# ft232.net
KiCad netlist of a schematic drawn in Altium Designer
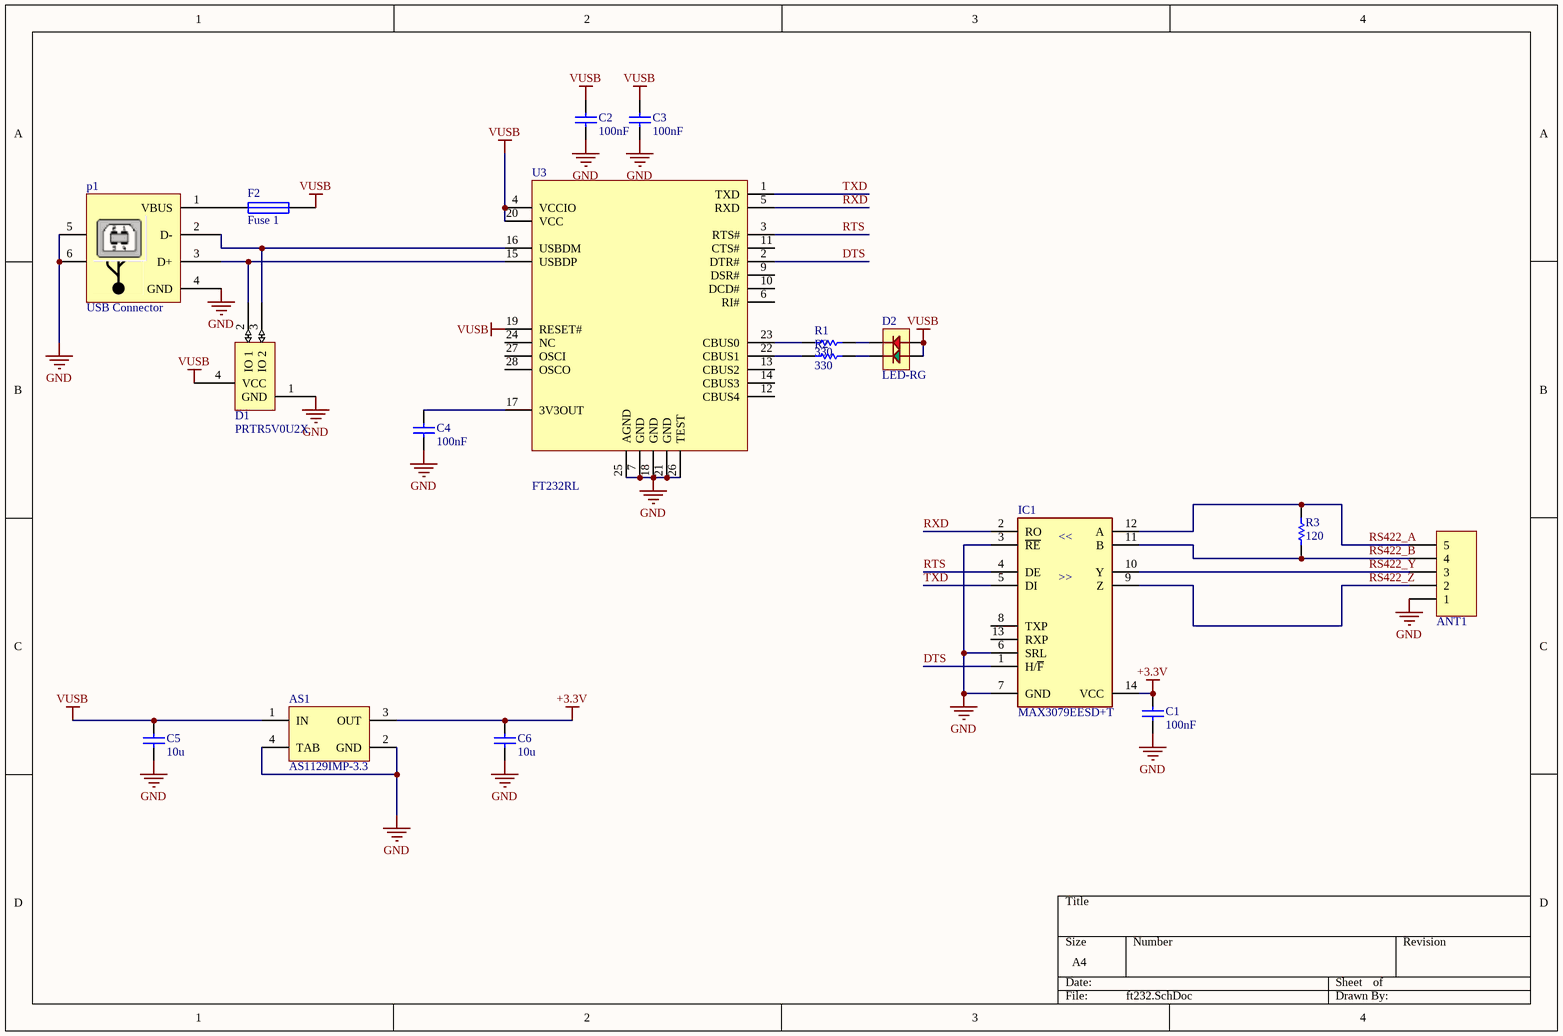
[diagram p0: ft232.SchDoc]

(export (version "E")
  (design (tool "Eeschema 10.0.6"))
  (components
    (comp (ref "ANT1") (value "CONN-5") (footprint "PH-5") (libsource (lib "ParsaLibrary") (part "CONN-5")))
    (comp (ref "AS1")
      (value "AS1129IMP-3.3")
      (footprint "SOT-223")
      (description "x.x Volt, 800mA Low-Dropout Linear Regulator, 4-pin SOT-223")
      (fields
        (field (name "PARTNUMBER") "LM1117IMP-3.3")
        (field (name "MANUFACTURER") "National Semiconductor")
        (field (name "PUBLISHER") "Altium Limited")
      )
      (libsource (lib "ParsaLibrary") (part "AS1129IMP-x.x"))
    )
    (comp (ref "C1")
      (value "100nF")
      (footprint "C603")
      (description "Capacitor")
      (fields (field (name "DESIGNER") "Parsa Malekpour"))
      (libsource (lib "ParsaLibrary") (part "Cap"))
    )
    (comp (ref "C2")
      (value "100nF")
      (footprint "c603")
      (description "Capacitor")
      (fields (field (name "DESIGNER") "Parsa Malekpour"))
      (libsource (lib "ParsaLibrary") (part "Cap"))
    )
    (comp (ref "C3")
      (value "100nF")
      (footprint "c603")
      (description "Capacitor")
      (fields (field (name "DESIGNER") "Parsa Malekpour"))
      (libsource (lib "ParsaLibrary") (part "Cap"))
    )
    (comp (ref "C4")
      (value "100nF")
      (footprint "c603")
      (description "Capacitor")
      (fields (field (name "DESIGNER") "Parsa Malekpour"))
      (libsource (lib "ParsaLibrary") (part "Cap"))
    )
    (comp (ref "C5")
      (value "10u")
      (footprint "C603")
      (description "Capacitor")
      (fields (field (name "DESIGNER") "Parsa Malekpour"))
      (libsource (lib "ParsaLibrary") (part "Cap"))
    )
    (comp (ref "C6")
      (value "10u")
      (footprint "C603")
      (description "Capacitor")
      (fields (field (name "DESIGNER") "Parsa Malekpour"))
      (libsource (lib "ParsaLibrary") (part "Cap"))
    )
    (comp (ref "D1")
      (value "PRTR5V0U2X")
      (footprint "SOT-143B")
      (description "Ultra low capacitance double rail-to-rail ESD protection diode")
      (libsource (lib "ParsaLibrary") (part "PRTR5V0U2X"))
    )
    (comp (ref "D2")
      (value "LED-RG")
      (footprint "LED-1210")
      (libsource (lib "ParsaLibrary") (part "LED-RG-4"))
    )
    (comp (ref "F2")
      (value "Fuse 1")
      (footprint "PTC-0805")
      (description "Fuse")
      (fields (field (name "PUBLISHER") "Altium Limited"))
      (libsource (lib "Miscellaneous Devices") (part "Fuse 1"))
    )
    (comp (ref "IC1")
      (value "MAX3079EESD+T")
      (footprint "SamacSys:SOIC127P600X175-14N")
      (description "Integrated Circuit")
      (fields (field (name "MOUSER PART NUMBER") "700-MAX3079EESDT"))
      (libsource (lib "SamacSys") (part "MAX3079EESD+T"))
    )
    (comp (ref "p1")
      (value "USB Connector")
      (footprint "USB2-B-R")
      (description "USB Connector-B Type")
      (fields (field (name "DESIGNER") "Eng. Saeid Jorablo"))
      (libsource (lib "ParsaLibrary") (part "USB2-B"))
    )
    (comp (ref "R1")
      (value "330")
      (footprint "R0603")
      (description "Resistor")
      (fields (field (name "DESIGNER") "Parsa Malekpour"))
      (libsource (lib "ParsaLibrary") (part "Resistor"))
    )
    (comp (ref "R2")
      (value "330")
      (footprint "R0603")
      (description "Resistor")
      (fields (field (name "DESIGNER") "Parsa Malekpour"))
      (libsource (lib "ParsaLibrary") (part "Resistor"))
    )
    (comp (ref "R3")
      (value "120")
      (footprint "R0603")
      (description "Resistor")
      (fields (field (name "DESIGNER") "Parsa Malekpour"))
      (libsource (lib "ParsaLibrary") (part "Resistor"))
    )
    (comp (ref "U3")
      (value "FT232RL")
      (footprint "SSOP-28N")
      (libsource (lib "ParsaLibrary") (part "FT232RL"))
    )
  )
  (nets
    (net (code "1") (name "+3.3V") (class "Default")
      (node (ref "AS1") (pin "3") (pinfunction "OUT_3") (pintype "power_in"))
      (node (ref "C1") (pin "2") (pinfunction "2_2") (pintype "passive"))
      (node (ref "C6") (pin "2") (pinfunction "2_2") (pintype "passive"))
      (node (ref "IC1") (pin "14") (pinfunction "VCC_14") (pintype "passive"))
    )
    (net (code "2") (name "/DTS") (class "Default")
      (node (ref "IC1") (pin "1") (pinfunction "H/~{F}_1") (pintype "passive"))
      (node (ref "U3") (pin "2") (pinfunction "DTR#_2") (pintype "passive"))
    )
    (net (code "3") (name "/RS422_A") (class "Default")
      (node (ref "ANT1") (pin "5") (pinfunction "5_5") (pintype "passive"))
      (node (ref "IC1") (pin "12") (pinfunction "A_12") (pintype "passive"))
      (node (ref "R3") (pin "2") (pinfunction "2_2") (pintype "passive"))
    )
    (net (code "4") (name "/RS422_B") (class "Default")
      (node (ref "ANT1") (pin "4") (pinfunction "4_4") (pintype "passive"))
      (node (ref "IC1") (pin "11") (pinfunction "B_11") (pintype "passive"))
      (node (ref "R3") (pin "1") (pinfunction "1_1") (pintype "passive"))
    )
    (net (code "5") (name "/RS422_Y") (class "Default")
      (node (ref "ANT1") (pin "3") (pinfunction "3_3") (pintype "passive"))
      (node (ref "IC1") (pin "10") (pinfunction "Y_10") (pintype "passive"))
    )
    (net (code "6") (name "/RS422_Z") (class "Default")
      (node (ref "ANT1") (pin "2") (pinfunction "2_2") (pintype "passive"))
      (node (ref "IC1") (pin "9") (pinfunction "Z_9") (pintype "passive"))
    )
    (net (code "7") (name "/RTS") (class "Default")
      (node (ref "IC1") (pin "4") (pinfunction "DE_4") (pintype "passive"))
      (node (ref "U3") (pin "3") (pinfunction "RTS#_3") (pintype "passive"))
    )
    (net (code "8") (name "/RXD") (class "Default")
      (node (ref "IC1") (pin "2") (pinfunction "RO_2") (pintype "passive"))
      (node (ref "U3") (pin "5") (pinfunction "RXD_5") (pintype "passive"))
    )
    (net (code "9") (name "/TXD") (class "Default")
      (node (ref "IC1") (pin "5") (pinfunction "DI_5") (pintype "passive"))
      (node (ref "U3") (pin "1") (pinfunction "TXD_1") (pintype "passive"))
    )
    (net (code "10") (name "GND") (class "Default")
      (node (ref "ANT1") (pin "1") (pinfunction "1_1") (pintype "passive"))
      (node (ref "AS1") (pin "2") (pinfunction "GND_2") (pintype "power_in"))
      (node (ref "AS1") (pin "4") (pinfunction "TAB_4") (pintype "power_in"))
      (node (ref "C1") (pin "1") (pinfunction "1_1") (pintype "passive"))
      (node (ref "C2") (pin "1") (pinfunction "1_1") (pintype "passive"))
      (node (ref "C3") (pin "1") (pinfunction "1_1") (pintype "passive"))
      (node (ref "C4") (pin "1") (pinfunction "1_1") (pintype "passive"))
      (node (ref "C5") (pin "1") (pinfunction "1_1") (pintype "passive"))
      (node (ref "C6") (pin "1") (pinfunction "1_1") (pintype "passive"))
      (node (ref "D1") (pin "1") (pinfunction "GND_1") (pintype "power_in"))
      (node (ref "IC1") (pin "3") (pinfunction "~{RE}_3") (pintype "passive"))
      (node (ref "IC1") (pin "6") (pinfunction "SRL_6") (pintype "passive"))
      (node (ref "IC1") (pin "7") (pinfunction "GND_7") (pintype "passive"))
      (node (ref "U3") (pin "18") (pinfunction "GND_18") (pintype "passive"))
      (node (ref "U3") (pin "21") (pinfunction "GND_21") (pintype "passive"))
      (node (ref "U3") (pin "25") (pinfunction "AGND_25") (pintype "passive"))
      (node (ref "U3") (pin "26") (pinfunction "TEST_26") (pintype "passive"))
      (node (ref "U3") (pin "7") (pinfunction "GND_7") (pintype "passive"))
      (node (ref "p1") (pin "4") (pinfunction "GND_4") (pintype "power_in"))
      (node (ref "p1") (pin "5") (pinfunction "5_5") (pintype "passive"))
      (node (ref "p1") (pin "6") (pinfunction "6_6") (pintype "passive"))
    )
    (net (code "11") (name "Net-(D1-IO_1)") (class "Default")
      (node (ref "D1") (pin "2") (pinfunction "IO_1_2") (pintype "bidirectional"))
      (node (ref "U3") (pin "15") (pinfunction "USBDP_15") (pintype "passive"))
      (node (ref "p1") (pin "3") (pinfunction "D+_3") (pintype "passive"))
    )
    (net (code "12") (name "Net-(D1-IO_2)") (class "Default")
      (node (ref "D1") (pin "3") (pinfunction "IO_2_3") (pintype "bidirectional"))
      (node (ref "U3") (pin "16") (pinfunction "USBDM_16") (pintype "passive"))
      (node (ref "p1") (pin "2") (pinfunction "D-_2") (pintype "passive"))
    )
    (net (code "13") (name "Net-(D2-GRN-C)") (class "Default")
      (node (ref "D2") (pin "4") (pinfunction "GRN-C_4") (pintype "passive"))
      (node (ref "R2") (pin "2") (pinfunction "2_2") (pintype "passive"))
    )
    (net (code "14") (name "Net-(D2-RED-C)") (class "Default")
      (node (ref "D2") (pin "3") (pinfunction "RED-C_3") (pintype "passive"))
      (node (ref "R1") (pin "2") (pinfunction "2_2") (pintype "passive"))
    )
    (net (code "15") (name "Net-(U3-3V3OUT)") (class "Default")
      (node (ref "C4") (pin "2") (pinfunction "2_2") (pintype "passive"))
      (node (ref "U3") (pin "17") (pinfunction "3V3OUT_17") (pintype "passive"))
    )
    (net (code "16") (name "Net-(U3-CBUS0)") (class "Default")
      (node (ref "R1") (pin "1") (pinfunction "1_1") (pintype "passive"))
      (node (ref "U3") (pin "23") (pinfunction "CBUS0_23") (pintype "passive"))
    )
    (net (code "17") (name "Net-(U3-CBUS1)") (class "Default")
      (node (ref "R2") (pin "1") (pinfunction "1_1") (pintype "passive"))
      (node (ref "U3") (pin "22") (pinfunction "CBUS1_22") (pintype "passive"))
    )
    (net (code "18") (name "Net-(p1-VBUS)") (class "Default")
      (node (ref "F2") (pin "1") (pinfunction "1_1") (pintype "passive"))
      (node (ref "p1") (pin "1") (pinfunction "VBUS_1") (pintype "power_in"))
    )
    (net (code "19") (name "VUSB") (class "Default")
      (node (ref "AS1") (pin "1") (pinfunction "IN_1") (pintype "power_in"))
      (node (ref "C2") (pin "2") (pinfunction "2_2") (pintype "passive"))
      (node (ref "C3") (pin "2") (pinfunction "2_2") (pintype "passive"))
      (node (ref "C5") (pin "2") (pinfunction "2_2") (pintype "passive"))
      (node (ref "D1") (pin "4") (pinfunction "VCC_4") (pintype "power_in"))
      (node (ref "D2") (pin "1") (pinfunction "GRN-A_1") (pintype "passive"))
      (node (ref "D2") (pin "2") (pinfunction "RED-A_2") (pintype "passive"))
      (node (ref "F2") (pin "2") (pinfunction "2_2") (pintype "passive"))
      (node (ref "U3") (pin "19") (pinfunction "RESET#_19") (pintype "passive"))
      (node (ref "U3") (pin "20") (pinfunction "VCC_20") (pintype "passive"))
      (node (ref "U3") (pin "4") (pinfunction "VCCIO_4") (pintype "passive"))
    )
    (net (code "20") (name "unconnected-(IC1-RXP-Pad13)") (class "Default")
      (node (ref "IC1") (pin "13") (pinfunction "RXP_13") (pintype "passive"))
    )
    (net (code "21") (name "unconnected-(IC1-TXP-Pad8)") (class "Default")
      (node (ref "IC1") (pin "8") (pinfunction "TXP_8") (pintype "passive"))
    )
    (net (code "22") (name "unconnected-(U3-CBUS2-Pad13)") (class "Default")
      (node (ref "U3") (pin "13") (pinfunction "CBUS2_13") (pintype "passive"))
    )
    (net (code "23") (name "unconnected-(U3-CBUS3-Pad14)") (class "Default")
      (node (ref "U3") (pin "14") (pinfunction "CBUS3_14") (pintype "passive"))
    )
    (net (code "24") (name "unconnected-(U3-CBUS4-Pad12)") (class "Default")
      (node (ref "U3") (pin "12") (pinfunction "CBUS4_12") (pintype "passive"))
    )
    (net (code "25") (name "unconnected-(U3-CTS#-Pad11)") (class "Default")
      (node (ref "U3") (pin "11") (pinfunction "CTS#_11") (pintype "passive"))
    )
    (net (code "26") (name "unconnected-(U3-DCD#-Pad10)") (class "Default")
      (node (ref "U3") (pin "10") (pinfunction "DCD#_10") (pintype "passive"))
    )
    (net (code "27") (name "unconnected-(U3-DSR#-Pad9)") (class "Default")
      (node (ref "U3") (pin "9") (pinfunction "DSR#_9") (pintype "passive"))
    )
    (net (code "28") (name "unconnected-(U3-NC-Pad8)") (class "Default")
      (node (ref "U3") (pin "8") (pinfunction "NC_8") (pintype "passive"))
    )
    (net (code "29") (name "unconnected-(U3-NC-Pad24)") (class "Default")
      (node (ref "U3") (pin "24") (pinfunction "NC_24") (pintype "passive"))
    )
    (net (code "30") (name "unconnected-(U3-OSCI-Pad27)") (class "Default")
      (node (ref "U3") (pin "27") (pinfunction "OSCI_27") (pintype "passive"))
    )
    (net (code "31") (name "unconnected-(U3-OSCO-Pad28)") (class "Default")
      (node (ref "U3") (pin "28") (pinfunction "OSCO_28") (pintype "passive"))
    )
    (net (code "32") (name "unconnected-(U3-RI#-Pad6)") (class "Default")
      (node (ref "U3") (pin "6") (pinfunction "RI#_6") (pintype "passive"))
    )
  )
)
